# mulemachinePCB_withLEDs.net
KiCad netlist of a schematic drawn in EAGLE
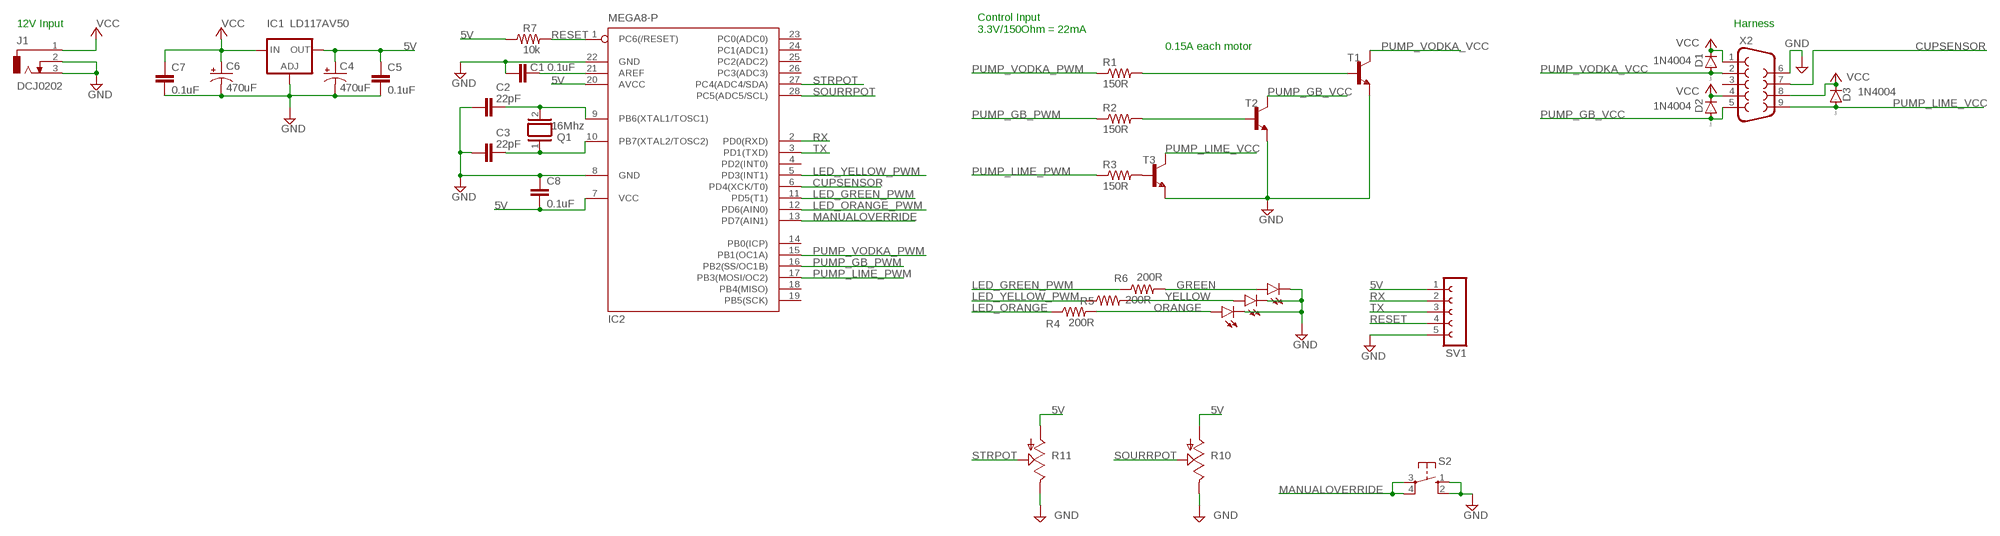
[diagram p0: schematic, sheet 1]

(export (version "E")
  (design (tool "Eeschema 10.0.6"))
  (components
    (comp (ref "C1")
      (value "0.1uF")
      (footprint "eagle-import:C2.5-3")
      (libsource (lib "eagle-import") (part "C2,5-3"))
    )
    (comp (ref "C2")
      (value "22pF")
      (footprint "eagle-import:C2.5-3")
      (libsource (lib "eagle-import") (part "C2,5-3"))
    )
    (comp (ref "C3")
      (value "22pF")
      (footprint "eagle-import:C2.5-3")
      (libsource (lib "eagle-import") (part "C2,5-3"))
    )
    (comp (ref "C4")
      (value "470uF")
      (footprint "eagle-import:E2,5-6")
      (libsource (lib "eagle-import") (part "CPOL-USE2.5-6"))
    )
    (comp (ref "C5")
      (value "0.1uF")
      (footprint "eagle-import:C2.5-3")
      (libsource (lib "eagle-import") (part "C2,5-3"))
    )
    (comp (ref "C6")
      (value "470uF")
      (footprint "eagle-import:E2,5-6")
      (libsource (lib "eagle-import") (part "CPOL-USE2.5-6"))
    )
    (comp (ref "C7")
      (value "0.1uF")
      (footprint "eagle-import:C2.5-3")
      (libsource (lib "eagle-import") (part "C2,5-3"))
    )
    (comp (ref "C8")
      (value "0.1uF")
      (footprint "eagle-import:C2.5-3")
      (libsource (lib "eagle-import") (part "C2,5-3"))
    )
    (comp (ref "D1")
      (value "1N4004")
      (footprint "eagle-import:DO41-10")
      (libsource (lib "eagle-import") (part "1N4004"))
    )
    (comp (ref "D2")
      (value "1N4004")
      (footprint "eagle-import:DO41-10")
      (libsource (lib "eagle-import") (part "1N4004"))
    )
    (comp (ref "D3")
      (value "1N4004")
      (footprint "eagle-import:DO41-10")
      (libsource (lib "eagle-import") (part "1N4004"))
    )
    (comp (ref "IC1")
      (value "LD117AV50")
      (footprint "eagle-import:TO220L1")
      (libsource (lib "eagle-import") (part "LD117A?V50"))
    )
    (comp (ref "IC2")
      (value "MEGA8-P")
      (footprint "eagle-import:DIL28-3")
      (libsource (lib "eagle-import") (part "MEGA8-P"))
    )
    (comp (ref "J1")
      (value "DCJ0202")
      (footprint "eagle-import:DCJ0202")
      (libsource (lib "eagle-import") (part "DCJ0202"))
    )
    (comp (ref "LED1")
      (value "LED5MM")
      (footprint "eagle-import:LED5MM")
      (libsource (lib "eagle-import") (part "LED5MM"))
    )
    (comp (ref "LED2")
      (value "LED5MM")
      (footprint "eagle-import:LED5MM")
      (libsource (lib "eagle-import") (part "LED5MM"))
    )
    (comp (ref "LED3")
      (value "LED5MM")
      (footprint "eagle-import:LED5MM")
      (libsource (lib "eagle-import") (part "LED5MM"))
    )
    (comp (ref "Q1")
      (value "16Mhz")
      (footprint "eagle-import:QS")
      (libsource (lib "eagle-import") (part "XTAL/S"))
    )
    (comp (ref "R1")
      (value "150R")
      (footprint "eagle-import:0411_12")
      (libsource (lib "eagle-import") (part "R-US_0411/12"))
    )
    (comp (ref "R2")
      (value "150R")
      (footprint "eagle-import:0411_12")
      (libsource (lib "eagle-import") (part "R-US_0411/12"))
    )
    (comp (ref "R3")
      (value "150R")
      (footprint "eagle-import:0411_12")
      (libsource (lib "eagle-import") (part "R-US_0411/12"))
    )
    (comp (ref "R4")
      (value "200R")
      (footprint "eagle-import:0411_12")
      (libsource (lib "eagle-import") (part "R-US_0411/12"))
    )
    (comp (ref "R5")
      (value "200R")
      (footprint "eagle-import:0411_12")
      (libsource (lib "eagle-import") (part "R-US_0411/12"))
    )
    (comp (ref "R6")
      (value "200R")
      (footprint "eagle-import:0411_12")
      (libsource (lib "eagle-import") (part "R-US_0411/12"))
    )
    (comp (ref "R7")
      (value "10k")
      (footprint "eagle-import:0207_10")
      (libsource (lib "eagle-import") (part "R-US_0207/10"))
    )
    (comp (ref "R10")
      (value "US-EVUF3L")
      (footprint "eagle-import:EVUFXL")
      (libsource (lib "eagle-import") (part "US-EVULF3"))
    )
    (comp (ref "R11")
      (value "US-EVUF3L")
      (footprint "eagle-import:EVUFXL")
      (libsource (lib "eagle-import") (part "US-EVULF3"))
    )
    (comp (ref "S2")
      (value "10-XX")
      (footprint "eagle-import:B3F-10XX")
      (fields (field (name "MPN") "B3F-1000"))
      (libsource (lib "eagle-import") (part "10-XX"))
    )
    (comp (ref "SV1")
      (value "FE05-1")
      (footprint "eagle-import:FE05-1")
      (libsource (lib "eagle-import") (part "FE05-1"))
    )
    (comp (ref "T1")
      (value "2N4401-NPN-TO92-EBC")
      (footprint "eagle-import:TO92-EBC")
      (libsource (lib "eagle-import") (part "-NPN-TO92-EBC2N4401"))
    )
    (comp (ref "T2")
      (value "2N4401-NPN-TO92-EBC")
      (footprint "eagle-import:TO92-EBC")
      (libsource (lib "eagle-import") (part "-NPN-TO92-EBC2N4401"))
    )
    (comp (ref "T3")
      (value "2N4401-NPN-TO92-EBC")
      (footprint "eagle-import:TO92-EBC")
      (libsource (lib "eagle-import") (part "-NPN-TO92-EBC2N4401"))
    )
    (comp (ref "X2")
      (value "F09HP")
      (footprint "eagle-import:F09HP")
      (libsource (lib "eagle-import") (part "F09HP"))
    )
  )
  (nets
    (net (code "1") (name "/5V") (class "Default")
      (node (ref "C4") (pin "+") (pinfunction "+_+") (pintype "passive"))
      (node (ref "C5") (pin "1") (pinfunction "1_1") (pintype "passive"))
      (node (ref "C8") (pin "2") (pinfunction "2_2") (pintype "passive"))
      (node (ref "IC1") (pin "2") (pinfunction "OUT_2") (pintype "passive"))
      (node (ref "IC2") (pin "20") (pinfunction "AVCC_20") (pintype "power_in"))
      (node (ref "IC2") (pin "7") (pinfunction "VCC_7") (pintype "power_in"))
      (node (ref "R10") (pin "1") (pinfunction "A_1") (pintype "passive"))
      (node (ref "R11") (pin "1") (pinfunction "A_1") (pintype "passive"))
      (node (ref "R7") (pin "1") (pinfunction "1_1") (pintype "passive"))
      (node (ref "SV1") (pin "1") (pinfunction "1_1") (pintype "passive"))
    )
    (net (code "2") (name "/CUPSENSOR") (class "Default")
      (node (ref "IC2") (pin "6") (pinfunction "PD4(XCK/T0)_6") (pintype "bidirectional"))
      (node (ref "X2") (pin "7") (pinfunction "7_7") (pintype "passive"))
    )
    (net (code "3") (name "/GREEN") (class "Default")
      (node (ref "LED3") (pin "A") (pinfunction "A_A") (pintype "passive"))
      (node (ref "R6") (pin "2") (pinfunction "2_2") (pintype "passive"))
    )
    (net (code "4") (name "/LED_GREEN_PWM") (class "Default")
      (node (ref "IC2") (pin "11") (pinfunction "PD5(T1)_11") (pintype "bidirectional"))
      (node (ref "R6") (pin "1") (pinfunction "1_1") (pintype "passive"))
    )
    (net (code "5") (name "/LED_ORANGE") (class "Default")
      (node (ref "R4") (pin "1") (pinfunction "1_1") (pintype "passive"))
    )
    (net (code "6") (name "/LED_ORANGE_PWM") (class "Default")
      (node (ref "IC2") (pin "12") (pinfunction "PD6(AIN0)_12") (pintype "bidirectional"))
    )
    (net (code "7") (name "/LED_YELLOW_PWM") (class "Default")
      (node (ref "IC2") (pin "5") (pinfunction "PD3(INT1)_5") (pintype "bidirectional"))
      (node (ref "R5") (pin "1") (pinfunction "1_1") (pintype "passive"))
    )
    (net (code "8") (name "/MANUALOVERRIDE") (class "Default")
      (node (ref "IC2") (pin "13") (pinfunction "PD7(AIN1)_13") (pintype "bidirectional"))
      (node (ref "S2") (pin "3") (pinfunction "P_3") (pintype "passive"))
      (node (ref "S2") (pin "4") (pinfunction "P1_4") (pintype "passive"))
    )
    (net (code "9") (name "/ORANGE") (class "Default")
      (node (ref "LED1") (pin "A") (pinfunction "A_A") (pintype "passive"))
      (node (ref "R4") (pin "2") (pinfunction "2_2") (pintype "passive"))
    )
    (net (code "10") (name "/PUMP_GB_PWM") (class "Default")
      (node (ref "IC2") (pin "16") (pinfunction "PB2(SS/OC1B)_16") (pintype "bidirectional"))
      (node (ref "R2") (pin "1") (pinfunction "1_1") (pintype "passive"))
    )
    (net (code "11") (name "/PUMP_GB_VCC") (class "Default")
      (node (ref "D2") (pin "A") (pinfunction "A_A") (pintype "passive"))
      (node (ref "T2") (pin "C") (pinfunction "C_C") (pintype "passive"))
      (node (ref "X2") (pin "5") (pinfunction "5_5") (pintype "passive"))
    )
    (net (code "12") (name "/PUMP_LIME_PWM") (class "Default")
      (node (ref "IC2") (pin "17") (pinfunction "PB3(MOSI/OC2)_17") (pintype "bidirectional"))
      (node (ref "R3") (pin "1") (pinfunction "1_1") (pintype "passive"))
    )
    (net (code "13") (name "/PUMP_LIME_VCC") (class "Default")
      (node (ref "D3") (pin "A") (pinfunction "A_A") (pintype "passive"))
      (node (ref "T3") (pin "C") (pinfunction "C_C") (pintype "passive"))
      (node (ref "X2") (pin "9") (pinfunction "9_9") (pintype "passive"))
    )
    (net (code "14") (name "/PUMP_VODKA_PWM") (class "Default")
      (node (ref "IC2") (pin "15") (pinfunction "PB1(OC1A)_15") (pintype "bidirectional"))
      (node (ref "R1") (pin "1") (pinfunction "1_1") (pintype "passive"))
    )
    (net (code "15") (name "/PUMP_VODKA_VCC") (class "Default")
      (node (ref "D1") (pin "A") (pinfunction "A_A") (pintype "passive"))
      (node (ref "T1") (pin "C") (pinfunction "C_C") (pintype "passive"))
      (node (ref "X2") (pin "2") (pinfunction "2_2") (pintype "passive"))
    )
    (net (code "16") (name "/RESET") (class "Default")
      (node (ref "IC2") (pin "1") (pinfunction "PC6(/RESET)_1") (pintype "bidirectional"))
      (node (ref "R7") (pin "2") (pinfunction "2_2") (pintype "passive"))
      (node (ref "SV1") (pin "4") (pinfunction "4_4") (pintype "passive"))
    )
    (net (code "17") (name "/RX") (class "Default")
      (node (ref "IC2") (pin "2") (pinfunction "PD0(RXD)_2") (pintype "bidirectional"))
      (node (ref "SV1") (pin "2") (pinfunction "2_2") (pintype "passive"))
    )
    (net (code "18") (name "/SOURRPOT") (class "Default")
      (node (ref "IC2") (pin "28") (pinfunction "PC5(ADC5/SCL)_28") (pintype "bidirectional"))
      (node (ref "R10") (pin "2") (pinfunction "S_2") (pintype "passive"))
    )
    (net (code "19") (name "/STRPOT") (class "Default")
      (node (ref "IC2") (pin "27") (pinfunction "PC4(ADC4/SDA)_27") (pintype "bidirectional"))
      (node (ref "R11") (pin "2") (pinfunction "S_2") (pintype "passive"))
    )
    (net (code "20") (name "/TX") (class "Default")
      (node (ref "IC2") (pin "3") (pinfunction "PD1(TXD)_3") (pintype "bidirectional"))
      (node (ref "SV1") (pin "3") (pinfunction "3_3") (pintype "passive"))
    )
    (net (code "21") (name "/YELLOW") (class "Default")
      (node (ref "LED2") (pin "A") (pinfunction "A_A") (pintype "passive"))
      (node (ref "R5") (pin "2") (pinfunction "2_2") (pintype "passive"))
    )
    (net (code "22") (name "GND") (class "Default")
      (node (ref "C1") (pin "2") (pinfunction "2_2") (pintype "passive"))
      (node (ref "C2") (pin "2") (pinfunction "2_2") (pintype "passive"))
      (node (ref "C3") (pin "2") (pinfunction "2_2") (pintype "passive"))
      (node (ref "C4") (pin "-") (pinfunction "-_-") (pintype "passive"))
      (node (ref "C5") (pin "2") (pinfunction "2_2") (pintype "passive"))
      (node (ref "C6") (pin "-") (pinfunction "-_-") (pintype "passive"))
      (node (ref "C7") (pin "2") (pinfunction "2_2") (pintype "passive"))
      (node (ref "C8") (pin "1") (pinfunction "1_1") (pintype "passive"))
      (node (ref "IC1") (pin "1") (pinfunction "ADJ_1") (pintype "input"))
      (node (ref "IC2") (pin "22") (pinfunction "GND_22") (pintype "power_in"))
      (node (ref "IC2") (pin "8") (pinfunction "GND_8") (pintype "power_in"))
      (node (ref "J1") (pin "2") (pinfunction "2_2") (pintype "passive"))
      (node (ref "J1") (pin "3") (pinfunction "3_3") (pintype "passive"))
      (node (ref "LED1") (pin "K") (pinfunction "C_K") (pintype "passive"))
      (node (ref "LED2") (pin "K") (pinfunction "C_K") (pintype "passive"))
      (node (ref "LED3") (pin "K") (pinfunction "C_K") (pintype "passive"))
      (node (ref "R10") (pin "3") (pinfunction "E_3") (pintype "passive"))
      (node (ref "R11") (pin "3") (pinfunction "E_3") (pintype "passive"))
      (node (ref "S2") (pin "1") (pinfunction "S_1") (pintype "passive"))
      (node (ref "S2") (pin "2") (pinfunction "S1_2") (pintype "passive"))
      (node (ref "SV1") (pin "5") (pinfunction "5_5") (pintype "passive"))
      (node (ref "T1") (pin "E") (pinfunction "E_E") (pintype "passive"))
      (node (ref "T2") (pin "E") (pinfunction "E_E") (pintype "passive"))
      (node (ref "T3") (pin "E") (pinfunction "E_E") (pintype "passive"))
      (node (ref "X2") (pin "6") (pinfunction "6_6") (pintype "passive"))
    )
    (net (code "23") (name "Net-(IC2-AREF)") (class "Default")
      (node (ref "C1") (pin "1") (pinfunction "1_1") (pintype "passive"))
      (node (ref "IC2") (pin "21") (pinfunction "AREF_21") (pintype "passive"))
    )
    (net (code "24") (name "Net-(IC2-PB6(XTAL1{slash}TOSC1))") (class "Default")
      (node (ref "C2") (pin "1") (pinfunction "1_1") (pintype "passive"))
      (node (ref "IC2") (pin "9") (pinfunction "PB6(XTAL1/TOSC1)_9") (pintype "bidirectional"))
      (node (ref "Q1") (pin "2") (pinfunction "2_2") (pintype "passive"))
    )
    (net (code "25") (name "Net-(IC2-PB7(XTAL2{slash}TOSC2))") (class "Default")
      (node (ref "C3") (pin "1") (pinfunction "1_1") (pintype "passive"))
      (node (ref "IC2") (pin "10") (pinfunction "PB7(XTAL2/TOSC2)_10") (pintype "bidirectional"))
      (node (ref "Q1") (pin "1") (pinfunction "1_1") (pintype "passive"))
    )
    (net (code "26") (name "Net-(R1-Pad2)") (class "Default")
      (node (ref "R1") (pin "2") (pinfunction "2_2") (pintype "passive"))
      (node (ref "T1") (pin "B") (pinfunction "B_B") (pintype "passive"))
    )
    (net (code "27") (name "Net-(R2-Pad2)") (class "Default")
      (node (ref "R2") (pin "2") (pinfunction "2_2") (pintype "passive"))
      (node (ref "T2") (pin "B") (pinfunction "B_B") (pintype "passive"))
    )
    (net (code "28") (name "Net-(R3-Pad2)") (class "Default")
      (node (ref "R3") (pin "2") (pinfunction "2_2") (pintype "passive"))
      (node (ref "T3") (pin "B") (pinfunction "B_B") (pintype "passive"))
    )
    (net (code "29") (name "VCC") (class "Default")
      (node (ref "C6") (pin "+") (pinfunction "+_+") (pintype "passive"))
      (node (ref "C7") (pin "1") (pinfunction "1_1") (pintype "passive"))
      (node (ref "D1") (pin "C") (pinfunction "C_C") (pintype "passive"))
      (node (ref "D2") (pin "C") (pinfunction "C_C") (pintype "passive"))
      (node (ref "D3") (pin "C") (pinfunction "C_C") (pintype "passive"))
      (node (ref "IC1") (pin "3") (pinfunction "IN_3") (pintype "input"))
      (node (ref "J1") (pin "1") (pinfunction "1_1") (pintype "passive"))
      (node (ref "X2") (pin "1") (pinfunction "1_1") (pintype "passive"))
      (node (ref "X2") (pin "4") (pinfunction "4_4") (pintype "passive"))
      (node (ref "X2") (pin "8") (pinfunction "8_8") (pintype "passive"))
    )
    (net (code "30") (name "unconnected-(IC2-PB0(ICP)-Pad14)") (class "Default")
      (node (ref "IC2") (pin "14") (pinfunction "PB0(ICP)_14") (pintype "bidirectional"))
    )
    (net (code "31") (name "unconnected-(IC2-PB4(MISO)-Pad18)") (class "Default")
      (node (ref "IC2") (pin "18") (pinfunction "PB4(MISO)_18") (pintype "bidirectional"))
    )
    (net (code "32") (name "unconnected-(IC2-PB5(SCK)-Pad19)") (class "Default")
      (node (ref "IC2") (pin "19") (pinfunction "PB5(SCK)_19") (pintype "bidirectional"))
    )
    (net (code "33") (name "unconnected-(IC2-PC0(ADC0)-Pad23)") (class "Default")
      (node (ref "IC2") (pin "23") (pinfunction "PC0(ADC0)_23") (pintype "bidirectional"))
    )
    (net (code "34") (name "unconnected-(IC2-PC1(ADC1)-Pad24)") (class "Default")
      (node (ref "IC2") (pin "24") (pinfunction "PC1(ADC1)_24") (pintype "bidirectional"))
    )
    (net (code "35") (name "unconnected-(IC2-PC2(ADC2)-Pad25)") (class "Default")
      (node (ref "IC2") (pin "25") (pinfunction "PC2(ADC2)_25") (pintype "bidirectional"))
    )
    (net (code "36") (name "unconnected-(IC2-PC3(ADC3)-Pad26)") (class "Default")
      (node (ref "IC2") (pin "26") (pinfunction "PC3(ADC3)_26") (pintype "bidirectional"))
    )
    (net (code "37") (name "unconnected-(IC2-PD2(INT0)-Pad4)") (class "Default")
      (node (ref "IC2") (pin "4") (pinfunction "PD2(INT0)_4") (pintype "bidirectional"))
    )
    (net (code "38") (name "unconnected-(X2-Pad3)") (class "Default")
      (node (ref "X2") (pin "3") (pinfunction "3_3") (pintype "passive"))
    )
  )
)
